# ZYNQ_34_35_and_QPSI.net
KiCad netlist of a schematic drawn in Altium Designer
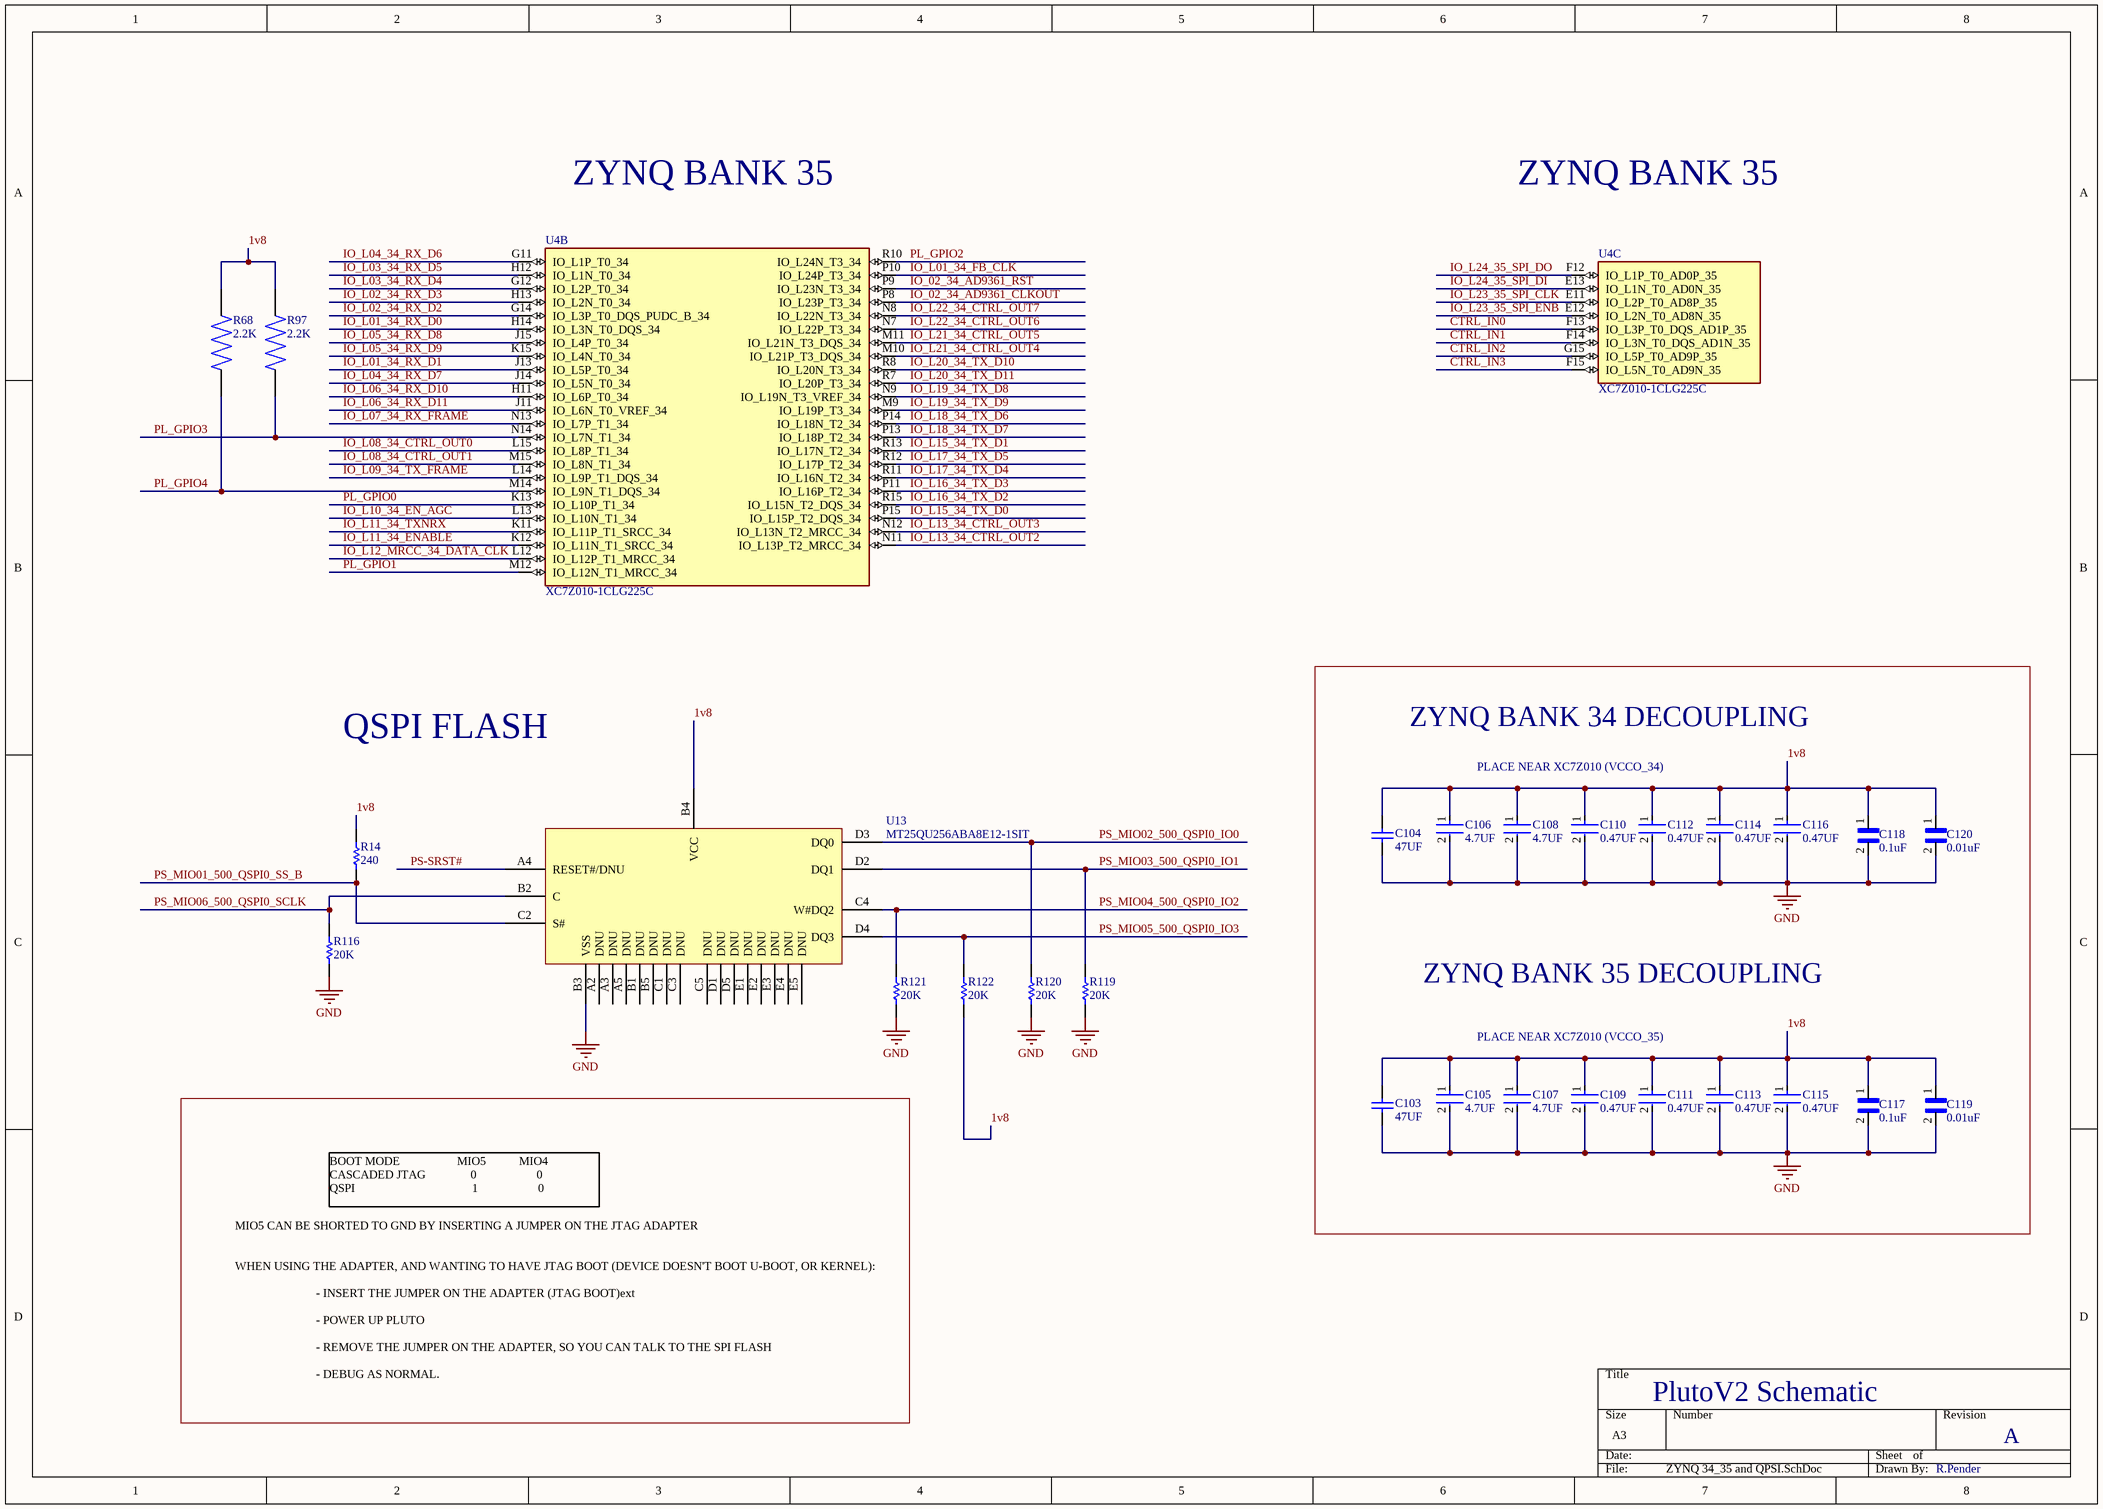
[diagram p0: ZYNQ 34_35 and QPSI.SchDoc]

(export (version "E")
  (design (tool "Eeschema 10.0.6"))
  (components
    (comp (ref "C103")
      (value "47UF")
      (footprint "TAYO-JMK212BBJ476MG-T_L")
      (fields
        (field (name "MANUFACTURER") "Taiyo Yuden")
        (field (name "TOLERANCE") "±20%")
        (field (name "PCN PART NUMBER") "X5R,X7RDielectrics23/Jan/2008")
      )
      (libsource (lib "Altium Content Vault") (part "CAP-NP-2"))
    )
    (comp (ref "C104")
      (value "47UF")
      (footprint "TAYO-JMK212BBJ476MG-T_L")
      (fields
        (field (name "MANUFACTURER") "Taiyo Yuden")
        (field (name "TOLERANCE") "±20%")
        (field (name "PCN PART NUMBER") "X5R,X7RDielectrics23/Jan/2008")
      )
      (libsource (lib "Altium Content Vault") (part "CAP-NP-2"))
    )
    (comp (ref "C105")
      (value "4.7UF")
      (footprint "FP-C1005-050-0_15-MFG")
      (description "CAP CER 4.7UF 6.3V X5R 0402")
      (fields (field (name "VOLTAGE") "6.3V") (field (name "TOLERANCE") "10%"))
      (libsource (lib "Altium Content Vault") (part "02cd4be3c70576c341d710602a673aa"))
    )
    (comp (ref "C106")
      (value "4.7UF")
      (footprint "FP-C1005-050-0_15-MFG")
      (description "CAP CER 4.7UF 6.3V X5R 0402")
      (fields (field (name "VOLTAGE") "6.3V") (field (name "TOLERANCE") "10%"))
      (libsource (lib "Altium Content Vault") (part "02cd4be3c70576c341d710602a673aa"))
    )
    (comp (ref "C107")
      (value "4.7UF")
      (footprint "FP-C1005-050-0_15-MFG")
      (description "CAP CER 4.7UF 6.3V X5R 0402")
      (fields (field (name "VOLTAGE") "6.3V") (field (name "TOLERANCE") "10%"))
      (libsource (lib "Altium Content Vault") (part "02cd4be3c70576c341d710602a673aa"))
    )
    (comp (ref "C108")
      (value "4.7UF")
      (footprint "FP-C1005-050-0_15-MFG")
      (description "CAP CER 4.7UF 6.3V X5R 0402")
      (fields (field (name "VOLTAGE") "6.3V") (field (name "TOLERANCE") "10%"))
      (libsource (lib "Altium Content Vault") (part "02cd4be3c70576c341d710602a673aa"))
    )
    (comp (ref "C109")
      (value "0.47UF")
      (footprint "FP-C1005-050-0_15-MFG")
      (description "CAP CER 4.7UF 6.3V X5R 0402")
      (fields (field (name "VOLTAGE") "6.3V") (field (name "TOLERANCE") "10%"))
      (libsource (lib "Altium Content Vault") (part "02cd4be3c70576c341d710602a673aa"))
    )
    (comp (ref "C110")
      (value "0.47UF")
      (footprint "FP-C1005-050-0_15-MFG")
      (description "CAP CER 4.7UF 6.3V X5R 0402")
      (fields (field (name "VOLTAGE") "6.3V") (field (name "TOLERANCE") "10%"))
      (libsource (lib "Altium Content Vault") (part "02cd4be3c70576c341d710602a673aa"))
    )
    (comp (ref "C111")
      (value "0.47UF")
      (footprint "FP-C1005-050-0_15-MFG")
      (description "CAP CER 4.7UF 6.3V X5R 0402")
      (fields (field (name "VOLTAGE") "6.3V") (field (name "TOLERANCE") "10%"))
      (libsource (lib "Altium Content Vault") (part "02cd4be3c70576c341d710602a673aa"))
    )
    (comp (ref "C112")
      (value "0.47UF")
      (footprint "FP-C1005-050-0_15-MFG")
      (description "CAP CER 4.7UF 6.3V X5R 0402")
      (fields (field (name "VOLTAGE") "6.3V") (field (name "TOLERANCE") "10%"))
      (libsource (lib "Altium Content Vault") (part "02cd4be3c70576c341d710602a673aa"))
    )
    (comp (ref "C113")
      (value "0.47UF")
      (footprint "FP-C1005-050-0_15-MFG")
      (description "CAP CER 4.7UF 6.3V X5R 0402")
      (fields (field (name "VOLTAGE") "6.3V") (field (name "TOLERANCE") "10%"))
      (libsource (lib "Altium Content Vault") (part "02cd4be3c70576c341d710602a673aa"))
    )
    (comp (ref "C114")
      (value "0.47UF")
      (footprint "FP-C1005-050-0_15-MFG")
      (description "CAP CER 4.7UF 6.3V X5R 0402")
      (fields (field (name "VOLTAGE") "6.3V") (field (name "TOLERANCE") "10%"))
      (libsource (lib "Altium Content Vault") (part "02cd4be3c70576c341d710602a673aa"))
    )
    (comp (ref "C115")
      (value "0.47UF")
      (footprint "FP-C1005-050-0_15-MFG")
      (description "CAP CER 4.7UF 6.3V X5R 0402")
      (fields (field (name "VOLTAGE") "6.3V") (field (name "TOLERANCE") "10%"))
      (libsource (lib "Altium Content Vault") (part "02cd4be3c70576c341d710602a673aa"))
    )
    (comp (ref "C116")
      (value "0.47UF")
      (footprint "FP-C1005-050-0_15-MFG")
      (description "CAP CER 4.7UF 6.3V X5R 0402")
      (fields (field (name "VOLTAGE") "6.3V") (field (name "TOLERANCE") "10%"))
      (libsource (lib "Altium Content Vault") (part "02cd4be3c70576c341d710602a673aa"))
    )
    (comp (ref "C117")
      (value "0.1uF")
      (footprint "CAPC0603X33N")
      (description "CAP 0.1UF 16VDC X5R 20% SMD 0201 PAPER TAPE")
      (fields (field (name "MP") "GRM033R61C104ME84D"))
      (libsource (lib "GRM033R61C104ME84D") (part "GRM033R61C104ME84D"))
    )
    (comp (ref "C118")
      (value "0.1uF")
      (footprint "CAPC0603X33N")
      (description "CAP 0.1UF 16VDC X5R 20% SMD 0201 PAPER TAPE")
      (fields (field (name "MP") "GRM033R61C104ME84D"))
      (libsource (lib "GRM033R61C104ME84D") (part "GRM033R61C104ME84D"))
    )
    (comp (ref "C119")
      (value "0.01uF")
      (footprint "CAPC0603X33N")
      (description "SMD Capacitor X7R(EIA) with Capacitance: 10000pF Tol. 10%. Rated Voltage: 10Vdc")
      (fields (field (name "MP") "GRM033R71A103KA01D") (field (name "MF") "Murata"))
      (libsource (lib "GRM033R71A103KA01D") (part "GRM033R71A103KA01D"))
    )
    (comp (ref "C120")
      (value "0.01uF")
      (footprint "CAPC0603X33N")
      (description "SMD Capacitor X7R(EIA) with Capacitance: 10000pF Tol. 10%. Rated Voltage: 10Vdc")
      (fields (field (name "MP") "GRM033R71A103KA01D") (field (name "MF") "Murata"))
      (libsource (lib "GRM033R71A103KA01D") (part "GRM033R71A103KA01D"))
    )
    (comp (ref "R14")
      (value "240")
      (footprint "2-0402")
      (fields (field (name "PUBLISHER") "Altium Limited"))
      (libsource (lib "Panasonic Resistor") (part "ERJ2RK"))
    )
    (comp (ref "R68")
      (value "2.2K")
      (footprint "RESC1005X35N")
      (description "2.2 kOhms Â±1% 0.063W, 1/16W Chip Resistor 0402 _1005 Metric_ Thick Film")
      (fields (field (name "MF") "Vishay") (field (name "MP") "CRCW04022K20FKEDC"))
      (libsource (lib "CRCW04022K20FKEDC") (part "CRCW04022K20FKEDC"))
    )
    (comp (ref "R97")
      (value "2.2K")
      (footprint "RESC1005X35N")
      (description "2.2 kOhms Â±1% 0.063W, 1/16W Chip Resistor 0402 _1005 Metric_ Thick Film")
      (fields (field (name "MF") "Vishay") (field (name "MP") "CRCW04022K20FKEDC"))
      (libsource (lib "CRCW04022K20FKEDC") (part "CRCW04022K20FKEDC"))
    )
    (comp (ref "R116")
      (value "20K")
      (footprint "2-0402")
      (fields (field (name "PUBLISHER") "Altium Limited"))
      (libsource (lib "Panasonic Resistor") (part "ERJ2RK"))
    )
    (comp (ref "R119")
      (value "20K")
      (footprint "2-0402")
      (fields (field (name "PUBLISHER") "Altium Limited"))
      (libsource (lib "Panasonic Resistor") (part "ERJ2RK"))
    )
    (comp (ref "R120")
      (value "20K")
      (footprint "2-0402")
      (fields (field (name "PUBLISHER") "Altium Limited"))
      (libsource (lib "Panasonic Resistor") (part "ERJ2RK"))
    )
    (comp (ref "R121")
      (value "20K")
      (footprint "2-0402")
      (fields (field (name "PUBLISHER") "Altium Limited"))
      (libsource (lib "Panasonic Resistor") (part "ERJ2RK"))
    )
    (comp (ref "R122")
      (value "20K")
      (footprint "2-0402")
      (fields (field (name "PUBLISHER") "Altium Limited"))
      (libsource (lib "Panasonic Resistor") (part "ERJ2RK"))
    )
    (comp (ref "U4")
      (value "XC7Z010-1CLG225C")
      (footprint "BGA225C80P15X15_1300X1300X150")
      (fields (field (name "MF") "Xilinx Inc.") (field (name "DIGI-KEY_PART_NUMBER") "122-1855-ND"))
      (libsource (lib "XC7Z010-1CLG225C") (part "XC7Z010-1CLG225C"))
    )
    (comp (ref "U13")
      (value "MT25QU256ABA8E12-1SIT")
      (footprint "BGA25C100P5X5_800X600X120N")
      (libsource (lib "RINALDOSCHEMS") (part "Component_1"))
    )
  )
  (nets
    (net (code "1") (name "/1v8") (class "Default")
      (node (ref "C103") (pin "1") (pinfunction "1_1") (pintype "passive"))
      (node (ref "C104") (pin "1") (pinfunction "1_1") (pintype "passive"))
      (node (ref "C105") (pin "1") (pinfunction "1_1") (pintype "passive"))
      (node (ref "C106") (pin "1") (pinfunction "1_1") (pintype "passive"))
      (node (ref "C107") (pin "1") (pinfunction "1_1") (pintype "passive"))
      (node (ref "C108") (pin "1") (pinfunction "1_1") (pintype "passive"))
      (node (ref "C109") (pin "1") (pinfunction "1_1") (pintype "passive"))
      (node (ref "C110") (pin "1") (pinfunction "1_1") (pintype "passive"))
      (node (ref "C111") (pin "1") (pinfunction "1_1") (pintype "passive"))
      (node (ref "C112") (pin "1") (pinfunction "1_1") (pintype "passive"))
      (node (ref "C113") (pin "1") (pinfunction "1_1") (pintype "passive"))
      (node (ref "C114") (pin "1") (pinfunction "1_1") (pintype "passive"))
      (node (ref "C115") (pin "1") (pinfunction "1_1") (pintype "passive"))
      (node (ref "C116") (pin "1") (pinfunction "1_1") (pintype "passive"))
      (node (ref "C117") (pin "1") (pinfunction "1_1") (pintype "passive"))
      (node (ref "C118") (pin "1") (pinfunction "1_1") (pintype "passive"))
      (node (ref "C119") (pin "1") (pinfunction "1_1") (pintype "passive"))
      (node (ref "C120") (pin "1") (pinfunction "1_1") (pintype "passive"))
      (node (ref "R122") (pin "2") (pinfunction "2_2") (pintype "passive"))
      (node (ref "R14") (pin "1") (pinfunction "1_1") (pintype "passive"))
      (node (ref "R68") (pin "2") (pinfunction "2_2") (pintype "passive"))
      (node (ref "R97") (pin "2") (pinfunction "2_2") (pintype "passive"))
      (node (ref "U13") (pin "B4") (pinfunction "VCC_B4") (pintype "power_in"))
    )
    (net (code "2") (name "/CTRL_IN0") (class "Default")
      (node (ref "U4") (pin "F13") (pinfunction "IO_L3P_T0_DQS_AD1P_35_F13") (pintype "bidirectional"))
    )
    (net (code "3") (name "/CTRL_IN1") (class "Default")
      (node (ref "U4") (pin "F14") (pinfunction "IO_L3N_T0_DQS_AD1N_35_F14") (pintype "bidirectional"))
    )
    (net (code "4") (name "/CTRL_IN2") (class "Default")
      (node (ref "U4") (pin "G15") (pinfunction "IO_L5P_T0_AD9P_35_G15") (pintype "bidirectional"))
    )
    (net (code "5") (name "/CTRL_IN3") (class "Default")
      (node (ref "U4") (pin "F15") (pinfunction "IO_L5N_T0_AD9N_35_F15") (pintype "bidirectional"))
    )
    (net (code "6") (name "/IO_02_34_AD9361_CLKOUT") (class "Default")
      (node (ref "U4") (pin "P8") (pinfunction "IO_L23P_T3_34_P8") (pintype "bidirectional"))
    )
    (net (code "7") (name "/IO_02_34_AD9361_RST") (class "Default")
      (node (ref "U4") (pin "P9") (pinfunction "IO_L23N_T3_34_P9") (pintype "bidirectional"))
    )
    (net (code "8") (name "/IO_L01_34_FB_CLK") (class "Default")
      (node (ref "U4") (pin "P10") (pinfunction "IO_L24P_T3_34_P10") (pintype "bidirectional"))
    )
    (net (code "9") (name "/IO_L01_34_RX_D0") (class "Default")
      (node (ref "U4") (pin "H14") (pinfunction "IO_L3N_T0_DQS_34_H14") (pintype "bidirectional"))
    )
    (net (code "10") (name "/IO_L01_34_RX_D1") (class "Default")
      (node (ref "U4") (pin "J13") (pinfunction "IO_L5P_T0_34_J13") (pintype "bidirectional"))
    )
    (net (code "11") (name "/IO_L02_34_RX_D2") (class "Default")
      (node (ref "U4") (pin "G14") (pinfunction "IO_L3P_T0_DQS_PUDC_B_34_G14") (pintype "bidirectional"))
    )
    (net (code "12") (name "/IO_L02_34_RX_D3") (class "Default")
      (node (ref "U4") (pin "H13") (pinfunction "IO_L2N_T0_34_H13") (pintype "bidirectional"))
    )
    (net (code "13") (name "/IO_L03_34_RX_D4") (class "Default")
      (node (ref "U4") (pin "G12") (pinfunction "IO_L2P_T0_34_G12") (pintype "bidirectional"))
    )
    (net (code "14") (name "/IO_L03_34_RX_D5") (class "Default")
      (node (ref "U4") (pin "H12") (pinfunction "IO_L1N_T0_34_H12") (pintype "bidirectional"))
    )
    (net (code "15") (name "/IO_L04_34_RX_D6") (class "Default")
      (node (ref "U4") (pin "G11") (pinfunction "IO_L1P_T0_34_G11") (pintype "bidirectional"))
    )
    (net (code "16") (name "/IO_L04_34_RX_D7") (class "Default")
      (node (ref "U4") (pin "J14") (pinfunction "IO_L5N_T0_34_J14") (pintype "bidirectional"))
    )
    (net (code "17") (name "/IO_L05_34_RX_D8") (class "Default")
      (node (ref "U4") (pin "J15") (pinfunction "IO_L4P_T0_34_J15") (pintype "bidirectional"))
    )
    (net (code "18") (name "/IO_L05_34_RX_D9") (class "Default")
      (node (ref "U4") (pin "K15") (pinfunction "IO_L4N_T0_34_K15") (pintype "bidirectional"))
    )
    (net (code "19") (name "/IO_L06_34_RX_D10") (class "Default")
      (node (ref "U4") (pin "H11") (pinfunction "IO_L6P_T0_34_H11") (pintype "bidirectional"))
    )
    (net (code "20") (name "/IO_L06_34_RX_D11") (class "Default")
      (node (ref "U4") (pin "J11") (pinfunction "IO_L6N_T0_VREF_34_J11") (pintype "bidirectional"))
    )
    (net (code "21") (name "/IO_L07_34_RX_FRAME") (class "Default")
      (node (ref "U4") (pin "N13") (pinfunction "IO_L7P_T1_34_N13") (pintype "bidirectional"))
    )
    (net (code "22") (name "/IO_L08_34_CTRL_OUT0") (class "Default")
      (node (ref "U4") (pin "L15") (pinfunction "IO_L8P_T1_34_L15") (pintype "bidirectional"))
    )
    (net (code "23") (name "/IO_L08_34_CTRL_OUT1") (class "Default")
      (node (ref "U4") (pin "M15") (pinfunction "IO_L8N_T1_34_M15") (pintype "bidirectional"))
    )
    (net (code "24") (name "/IO_L09_34_TX_FRAME") (class "Default")
      (node (ref "U4") (pin "L14") (pinfunction "IO_L9P_T1_DQS_34_L14") (pintype "bidirectional"))
    )
    (net (code "25") (name "/IO_L10_34_EN_AGC") (class "Default")
      (node (ref "U4") (pin "L13") (pinfunction "IO_L10N_T1_34_L13") (pintype "bidirectional"))
    )
    (net (code "26") (name "/IO_L11_34_ENABLE") (class "Default")
      (node (ref "U4") (pin "K12") (pinfunction "IO_L11N_T1_SRCC_34_K12") (pintype "bidirectional"))
    )
    (net (code "27") (name "/IO_L11_34_TXNRX") (class "Default")
      (node (ref "U4") (pin "K11") (pinfunction "IO_L11P_T1_SRCC_34_K11") (pintype "bidirectional"))
    )
    (net (code "28") (name "/IO_L12_MRCC_34_DATA_CLK") (class "Default")
      (node (ref "U4") (pin "L12") (pinfunction "IO_L12P_T1_MRCC_34_L12") (pintype "bidirectional"))
    )
    (net (code "29") (name "/IO_L13_34_CTRL_OUT2") (class "Default")
      (node (ref "U4") (pin "N11") (pinfunction "IO_L13P_T2_MRCC_34_N11") (pintype "bidirectional"))
    )
    (net (code "30") (name "/IO_L13_34_CTRL_OUT3") (class "Default")
      (node (ref "U4") (pin "N12") (pinfunction "IO_L13N_T2_MRCC_34_N12") (pintype "bidirectional"))
    )
    (net (code "31") (name "/IO_L15_34_TX_D0") (class "Default")
      (node (ref "U4") (pin "P15") (pinfunction "IO_L15P_T2_DQS_34_P15") (pintype "bidirectional"))
    )
    (net (code "32") (name "/IO_L15_34_TX_D1") (class "Default")
      (node (ref "U4") (pin "R13") (pinfunction "IO_L17N_T2_34_R13") (pintype "bidirectional"))
    )
    (net (code "33") (name "/IO_L16_34_TX_D2") (class "Default")
      (node (ref "U4") (pin "R15") (pinfunction "IO_L15N_T2_DQS_34_R15") (pintype "bidirectional"))
    )
    (net (code "34") (name "/IO_L16_34_TX_D3") (class "Default")
      (node (ref "U4") (pin "P11") (pinfunction "IO_L16P_T2_34_P11") (pintype "bidirectional"))
    )
    (net (code "35") (name "/IO_L17_34_TX_D4") (class "Default")
      (node (ref "U4") (pin "R11") (pinfunction "IO_L16N_T2_34_R11") (pintype "bidirectional"))
    )
    (net (code "36") (name "/IO_L17_34_TX_D5") (class "Default")
      (node (ref "U4") (pin "R12") (pinfunction "IO_L17P_T2_34_R12") (pintype "bidirectional"))
    )
    (net (code "37") (name "/IO_L18_34_TX_D6") (class "Default")
      (node (ref "U4") (pin "P14") (pinfunction "IO_L18N_T2_34_P14") (pintype "bidirectional"))
    )
    (net (code "38") (name "/IO_L18_34_TX_D7") (class "Default")
      (node (ref "U4") (pin "P13") (pinfunction "IO_L18P_T2_34_P13") (pintype "bidirectional"))
    )
    (net (code "39") (name "/IO_L19_34_TX_D8") (class "Default")
      (node (ref "U4") (pin "N9") (pinfunction "IO_L19N_T3_VREF_34_N9") (pintype "bidirectional"))
    )
    (net (code "40") (name "/IO_L19_34_TX_D9") (class "Default")
      (node (ref "U4") (pin "M9") (pinfunction "IO_L19P_T3_34_M9") (pintype "bidirectional"))
    )
    (net (code "41") (name "/IO_L20_34_TX_D10") (class "Default")
      (node (ref "U4") (pin "R8") (pinfunction "IO_L20N_T3_34_R8") (pintype "bidirectional"))
    )
    (net (code "42") (name "/IO_L20_34_TX_D11") (class "Default")
      (node (ref "U4") (pin "R7") (pinfunction "IO_L20P_T3_34_R7") (pintype "bidirectional"))
    )
    (net (code "43") (name "/IO_L21_34_CTRL_OUT4") (class "Default")
      (node (ref "U4") (pin "M10") (pinfunction "IO_L21P_T3_DQS_34_M10") (pintype "bidirectional"))
    )
    (net (code "44") (name "/IO_L21_34_CTRL_OUT5") (class "Default")
      (node (ref "U4") (pin "M11") (pinfunction "IO_L21N_T3_DQS_34_M11") (pintype "bidirectional"))
    )
    (net (code "45") (name "/IO_L22_34_CTRL_OUT6") (class "Default")
      (node (ref "U4") (pin "N7") (pinfunction "IO_L22P_T3_34_N7") (pintype "bidirectional"))
    )
    (net (code "46") (name "/IO_L22_34_CTRL_OUT7") (class "Default")
      (node (ref "U4") (pin "N8") (pinfunction "IO_L22N_T3_34_N8") (pintype "bidirectional"))
    )
    (net (code "47") (name "/IO_L23_35_SPI_CLK") (class "Default")
      (node (ref "U4") (pin "E11") (pinfunction "IO_L2P_T0_AD8P_35_E11") (pintype "bidirectional"))
    )
    (net (code "48") (name "/IO_L23_35_SPI_ENB") (class "Default")
      (node (ref "U4") (pin "E12") (pinfunction "IO_L2N_T0_AD8N_35_E12") (pintype "bidirectional"))
    )
    (net (code "49") (name "/IO_L24_35_SPI_DI") (class "Default")
      (node (ref "U4") (pin "E13") (pinfunction "IO_L1N_T0_AD0N_35_E13") (pintype "bidirectional"))
    )
    (net (code "50") (name "/IO_L24_35_SPI_DO") (class "Default")
      (node (ref "U4") (pin "F12") (pinfunction "IO_L1P_T0_AD0P_35_F12") (pintype "bidirectional"))
    )
    (net (code "51") (name "/PL_GPIO0") (class "Default")
      (node (ref "U4") (pin "K13") (pinfunction "IO_L10P_T1_34_K13") (pintype "bidirectional"))
    )
    (net (code "52") (name "/PL_GPIO1") (class "Default")
      (node (ref "U4") (pin "M12") (pinfunction "IO_L12N_T1_MRCC_34_M12") (pintype "bidirectional"))
    )
    (net (code "53") (name "/PL_GPIO2") (class "Default")
      (node (ref "U4") (pin "R10") (pinfunction "IO_L24N_T3_34_R10") (pintype "bidirectional"))
    )
    (net (code "54") (name "/PL_GPIO3") (class "Default")
      (node (ref "R97") (pin "1") (pinfunction "1_1") (pintype "passive"))
      (node (ref "U4") (pin "N14") (pinfunction "IO_L7N_T1_34_N14") (pintype "bidirectional"))
    )
    (net (code "55") (name "/PL_GPIO4") (class "Default")
      (node (ref "R68") (pin "1") (pinfunction "1_1") (pintype "passive"))
      (node (ref "U4") (pin "M14") (pinfunction "IO_L9N_T1_DQS_34_M14") (pintype "bidirectional"))
    )
    (net (code "56") (name "/PS-SRST#") (class "Default")
      (node (ref "U13") (pin "A4") (pinfunction "RESET#/DNU_A4") (pintype "passive"))
    )
    (net (code "57") (name "/PS_MIO01_500_QSPI0_SS_B") (class "Default")
      (node (ref "R14") (pin "2") (pinfunction "2_2") (pintype "passive"))
      (node (ref "U13") (pin "C2") (pinfunction "S#_C2") (pintype "passive"))
    )
    (net (code "58") (name "/PS_MIO02_500_QSPI0_IO0") (class "Default")
      (node (ref "R120") (pin "1") (pinfunction "1_1") (pintype "passive"))
      (node (ref "U13") (pin "D3") (pinfunction "DQ0_D3") (pintype "passive"))
    )
    (net (code "59") (name "/PS_MIO03_500_QSPI0_IO1") (class "Default")
      (node (ref "R119") (pin "1") (pinfunction "1_1") (pintype "passive"))
      (node (ref "U13") (pin "D2") (pinfunction "DQ1_D2") (pintype "passive"))
    )
    (net (code "60") (name "/PS_MIO04_500_QSPI0_IO2") (class "Default")
      (node (ref "R121") (pin "1") (pinfunction "1_1") (pintype "passive"))
      (node (ref "U13") (pin "C4") (pinfunction "W#DQ2_C4") (pintype "passive"))
    )
    (net (code "61") (name "/PS_MIO05_500_QSPI0_IO3") (class "Default")
      (node (ref "R122") (pin "1") (pinfunction "1_1") (pintype "passive"))
      (node (ref "U13") (pin "D4") (pinfunction "DQ3_D4") (pintype "passive"))
    )
    (net (code "62") (name "/PS_MIO06_500_QSPI0_SCLK") (class "Default")
      (node (ref "R116") (pin "1") (pinfunction "1_1") (pintype "passive"))
      (node (ref "U13") (pin "B2") (pinfunction "C_B2") (pintype "passive"))
    )
    (net (code "63") (name "GND") (class "Default")
      (node (ref "C103") (pin "2") (pinfunction "2_2") (pintype "passive"))
      (node (ref "C104") (pin "2") (pinfunction "2_2") (pintype "passive"))
      (node (ref "C105") (pin "2") (pinfunction "2_2") (pintype "passive"))
      (node (ref "C106") (pin "2") (pinfunction "2_2") (pintype "passive"))
      (node (ref "C107") (pin "2") (pinfunction "2_2") (pintype "passive"))
      (node (ref "C108") (pin "2") (pinfunction "2_2") (pintype "passive"))
      (node (ref "C109") (pin "2") (pinfunction "2_2") (pintype "passive"))
      (node (ref "C110") (pin "2") (pinfunction "2_2") (pintype "passive"))
      (node (ref "C111") (pin "2") (pinfunction "2_2") (pintype "passive"))
      (node (ref "C112") (pin "2") (pinfunction "2_2") (pintype "passive"))
      (node (ref "C113") (pin "2") (pinfunction "2_2") (pintype "passive"))
      (node (ref "C114") (pin "2") (pinfunction "2_2") (pintype "passive"))
      (node (ref "C115") (pin "2") (pinfunction "2_2") (pintype "passive"))
      (node (ref "C116") (pin "2") (pinfunction "2_2") (pintype "passive"))
      (node (ref "C117") (pin "2") (pinfunction "2_2") (pintype "passive"))
      (node (ref "C118") (pin "2") (pinfunction "2_2") (pintype "passive"))
      (node (ref "C119") (pin "2") (pinfunction "2_2") (pintype "passive"))
      (node (ref "C120") (pin "2") (pinfunction "2_2") (pintype "passive"))
      (node (ref "R116") (pin "2") (pinfunction "2_2") (pintype "passive"))
      (node (ref "R119") (pin "2") (pinfunction "2_2") (pintype "passive"))
      (node (ref "R120") (pin "2") (pinfunction "2_2") (pintype "passive"))
      (node (ref "R121") (pin "2") (pinfunction "2_2") (pintype "passive"))
      (node (ref "U13") (pin "B3") (pinfunction "VSS_B3") (pintype "power_in"))
    )
    (net (code "64") (name "unconnected-(U13-DNU-PadA2)") (class "Default")
      (node (ref "U13") (pin "A2") (pinfunction "DNU_A2") (pintype "passive"))
    )
    (net (code "65") (name "unconnected-(U13-DNU-PadA3)") (class "Default")
      (node (ref "U13") (pin "A3") (pinfunction "DNU_A3") (pintype "passive"))
    )
    (net (code "66") (name "unconnected-(U13-DNU-PadA5)") (class "Default")
      (node (ref "U13") (pin "A5") (pinfunction "DNU_A5") (pintype "passive"))
    )
    (net (code "67") (name "unconnected-(U13-DNU-PadB1)") (class "Default")
      (node (ref "U13") (pin "B1") (pinfunction "DNU_B1") (pintype "passive"))
    )
    (net (code "68") (name "unconnected-(U13-DNU-PadB5)") (class "Default")
      (node (ref "U13") (pin "B5") (pinfunction "DNU_B5") (pintype "passive"))
    )
    (net (code "69") (name "unconnected-(U13-DNU-PadC1)") (class "Default")
      (node (ref "U13") (pin "C1") (pinfunction "DNU_C1") (pintype "passive"))
    )
    (net (code "70") (name "unconnected-(U13-DNU-PadC3)") (class "Default")
      (node (ref "U13") (pin "C3") (pinfunction "DNU_C3") (pintype "passive"))
    )
    (net (code "71") (name "unconnected-(U13-DNU-PadC5)") (class "Default")
      (node (ref "U13") (pin "C5") (pinfunction "DNU_C5") (pintype "passive"))
    )
    (net (code "72") (name "unconnected-(U13-DNU-PadD1)") (class "Default")
      (node (ref "U13") (pin "D1") (pinfunction "DNU_D1") (pintype "passive"))
    )
    (net (code "73") (name "unconnected-(U13-DNU-PadD5)") (class "Default")
      (node (ref "U13") (pin "D5") (pinfunction "DNU_D5") (pintype "passive"))
    )
    (net (code "74") (name "unconnected-(U13-DNU-PadE1)") (class "Default")
      (node (ref "U13") (pin "E1") (pinfunction "DNU_E1") (pintype "passive"))
    )
    (net (code "75") (name "unconnected-(U13-DNU-PadE2)") (class "Default")
      (node (ref "U13") (pin "E2") (pinfunction "DNU_E2") (pintype "passive"))
    )
    (net (code "76") (name "unconnected-(U13-DNU-PadE3)") (class "Default")
      (node (ref "U13") (pin "E3") (pinfunction "DNU_E3") (pintype "passive"))
    )
    (net (code "77") (name "unconnected-(U13-DNU-PadE4)") (class "Default")
      (node (ref "U13") (pin "E4") (pinfunction "DNU_E4") (pintype "passive"))
    )
    (net (code "78") (name "unconnected-(U13-DNU-PadE5)") (class "Default")
      (node (ref "U13") (pin "E5") (pinfunction "DNU_E5") (pintype "passive"))
    )
  )
)
